# mainboard.net
KiCad netlist of a schematic drawn in EAGLE
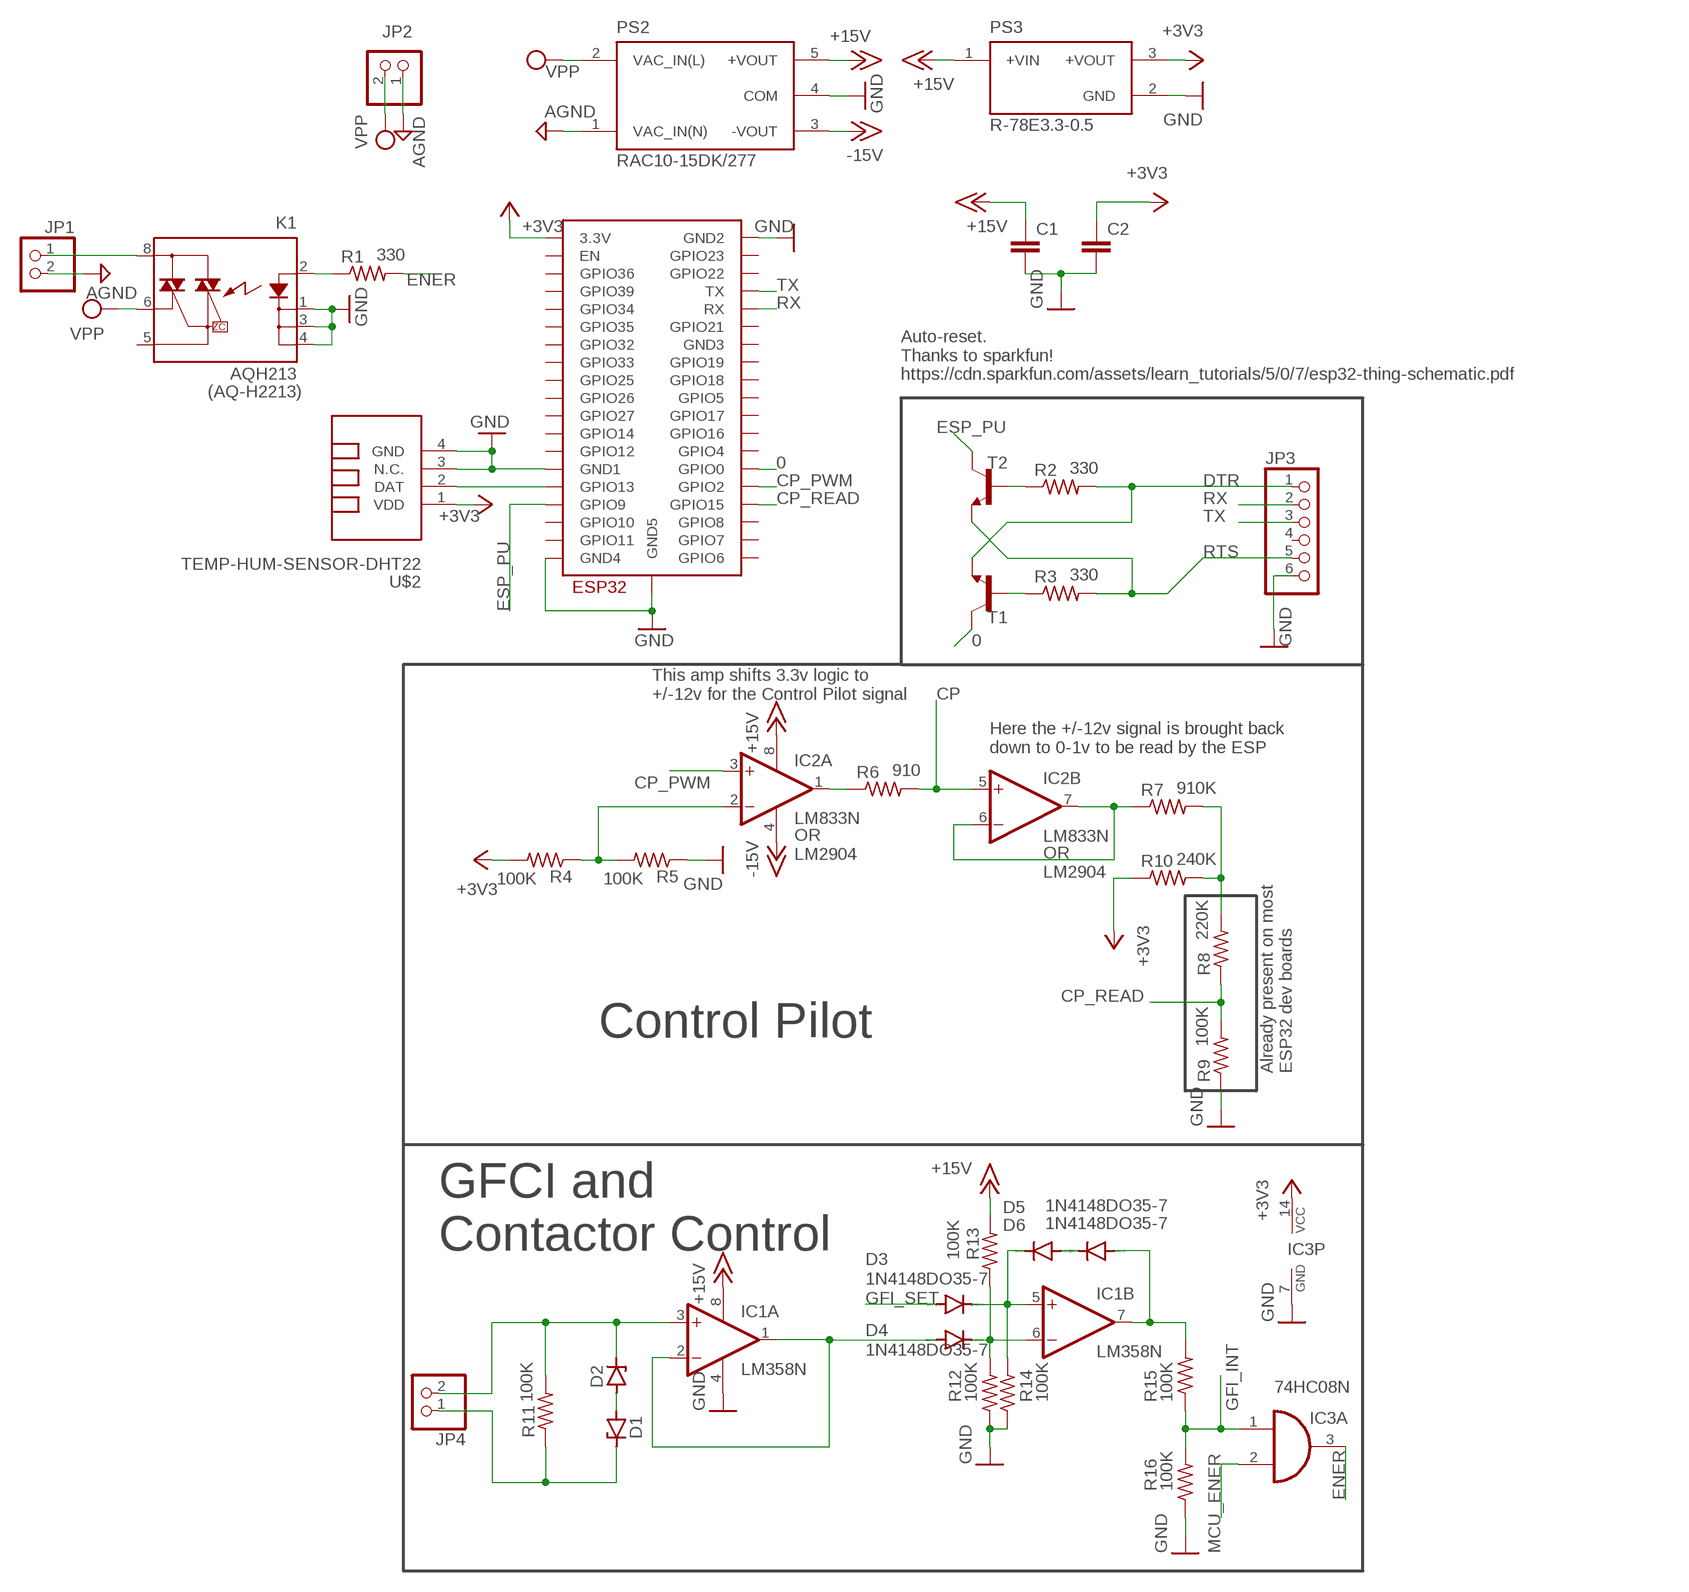
[diagram p0: schematic, sheet 1]

(export (version "E")
  (design (tool "Eeschema 10.0.6"))
  (components
    (comp (ref "C1")
      (value "C-EU025-025X050")
      (footprint "eagle-import:C025-025X050")
      (libsource (lib "eagle-import") (part "C-EU025-025X050"))
    )
    (comp (ref "C2")
      (value "C-EU025-025X050")
      (footprint "eagle-import:C025-025X050")
      (libsource (lib "eagle-import") (part "C-EU025-025X050"))
    )
    (comp (ref "D1")
      (value "ZENER-DIODEDO34-7")
      (footprint "eagle-import:DO34Z7")
      (libsource (lib "eagle-import") (part "ZENER-DIODEDO34-7"))
    )
    (comp (ref "D2")
      (value "ZENER-DIODEDO34-7")
      (footprint "eagle-import:DO34Z7")
      (libsource (lib "eagle-import") (part "ZENER-DIODEDO34-7"))
    )
    (comp (ref "D3")
      (value "1N4148DO35-7")
      (footprint "eagle-import:DO35-7")
      (libsource (lib "eagle-import") (part "1N4148DO35-7"))
    )
    (comp (ref "D4")
      (value "1N4148DO35-7")
      (footprint "eagle-import:DO35-7")
      (libsource (lib "eagle-import") (part "1N4148DO35-7"))
    )
    (comp (ref "D5")
      (value "1N4148DO35-7")
      (footprint "eagle-import:DO35-7")
      (libsource (lib "eagle-import") (part "1N4148DO35-7"))
    )
    (comp (ref "D6")
      (value "1N4148DO35-7")
      (footprint "eagle-import:DO35-7")
      (libsource (lib "eagle-import") (part "1N4148DO35-7"))
    )
    (comp (ref "IC1")
      (value "LM358N")
      (footprint "eagle-import:DIL08")
      (libsource (lib "eagle-import") (part "LM358N"))
    )
    (comp (ref "IC2")
      (value "LM833N")
      (footprint "eagle-import:DIL08")
      (libsource (lib "eagle-import") (part "LM833N"))
    )
    (comp (ref "IC3")
      (value "74HC08N")
      (footprint "eagle-import:DIL14")
      (libsource (lib "eagle-import") (part "7408NHC"))
    )
    (comp (ref "JP1")
      (value "PINHD-1X2")
      (footprint "eagle-import:1X02")
      (libsource (lib "eagle-import") (part "PINHD-1X2"))
    )
    (comp (ref "JP2")
      (value "PINHD-1X2")
      (footprint "eagle-import:1X02")
      (libsource (lib "eagle-import") (part "PINHD-1X2"))
    )
    (comp (ref "JP3")
      (value "PINHD-1X6")
      (footprint "eagle-import:1X06")
      (libsource (lib "eagle-import") (part "PINHD-1X6"))
    )
    (comp (ref "JP4")
      (value "PINHD-1X2")
      (footprint "eagle-import:1X02")
      (libsource (lib "eagle-import") (part "PINHD-1X2"))
    )
    (comp (ref "K1")
      (value "AQH213")
      (footprint "eagle-import:DIL07")
      (libsource (lib "eagle-import") (part "AQH213"))
    )
    (comp (ref "PS2")
      (value "RAC10-15DK/277")
      (footprint "eagle-import:CONV_RAC10-15DK_277")
      (fields (field (name "DIGI-KEY_PART_NUMBER") "945-3126-5-ND") (field (name "MF") "Recom Power"))
      (libsource (lib "eagle-import") (part "RAC10-15DK/277"))
    )
    (comp (ref "PS3")
      (value "R-78E3.3-0.5")
      (footprint "eagle-import:CONV_R-78E3.3-0.5")
      (fields (field (name "DIGI-KEY_PART_NUMBER") "945-1661-5-ND") (field (name "MF") "Recom Power"))
      (libsource (lib "eagle-import") (part "R-78E3.3-0.5"))
    )
    (comp (ref "R1")
      (value "330")
      (footprint "eagle-import:0204_7")
      (libsource (lib "eagle-import") (part "R-US_0204/7"))
    )
    (comp (ref "R2")
      (value "330")
      (footprint "eagle-import:0204_7")
      (libsource (lib "eagle-import") (part "R-US_0204/7"))
    )
    (comp (ref "R3")
      (value "330")
      (footprint "eagle-import:0204_7")
      (libsource (lib "eagle-import") (part "R-US_0204/7"))
    )
    (comp (ref "R4")
      (value "100K")
      (footprint "eagle-import:0204_7")
      (libsource (lib "eagle-import") (part "R-US_0204/7"))
    )
    (comp (ref "R5")
      (value "100K")
      (footprint "eagle-import:0204_7")
      (libsource (lib "eagle-import") (part "R-US_0204/7"))
    )
    (comp (ref "R6")
      (value "910")
      (footprint "eagle-import:0204_7")
      (libsource (lib "eagle-import") (part "R-US_0204/7"))
    )
    (comp (ref "R7")
      (value "910K")
      (footprint "eagle-import:0204_7")
      (libsource (lib "eagle-import") (part "R-US_0204/7"))
    )
    (comp (ref "R8")
      (value "220K")
      (footprint "eagle-import:0204_7")
      (libsource (lib "eagle-import") (part "R-US_0204/7"))
    )
    (comp (ref "R9")
      (value "100K")
      (footprint "eagle-import:0204_7")
      (libsource (lib "eagle-import") (part "R-US_0204/7"))
    )
    (comp (ref "R10")
      (value "240K")
      (footprint "eagle-import:0204_7")
      (libsource (lib "eagle-import") (part "R-US_0204/7"))
    )
    (comp (ref "R11")
      (value "100K")
      (footprint "eagle-import:0204_7")
      (libsource (lib "eagle-import") (part "R-US_0204/7"))
    )
    (comp (ref "R12")
      (value "100K")
      (footprint "eagle-import:0204_7")
      (libsource (lib "eagle-import") (part "R-US_0204/7"))
    )
    (comp (ref "R13")
      (value "100K")
      (footprint "eagle-import:0204_7")
      (libsource (lib "eagle-import") (part "R-US_0204/7"))
    )
    (comp (ref "R14")
      (value "100K")
      (footprint "eagle-import:0204_7")
      (libsource (lib "eagle-import") (part "R-US_0204/7"))
    )
    (comp (ref "R15")
      (value "100K")
      (footprint "eagle-import:0204_7")
      (libsource (lib "eagle-import") (part "R-US_0204/7"))
    )
    (comp (ref "R16")
      (value "100K")
      (footprint "eagle-import:0204_7")
      (libsource (lib "eagle-import") (part "R-US_0204/7"))
    )
    (comp (ref "T1")
      (value "MMBT3904LT1-NPN-SOT23-BEC")
      (footprint "eagle-import:SOT23-BEC")
      (libsource (lib "eagle-import") (part "-NPN-SOT23-BECMMBT3904LT1"))
    )
    (comp (ref "T2")
      (value "MMBT3904LT1-NPN-SOT23-BEC")
      (footprint "eagle-import:SOT23-BEC")
      (libsource (lib "eagle-import") (part "-NPN-SOT23-BECMMBT3904LT1"))
    )
    (comp (ref "U$1")
      (value "ESP32-WROOM")
      (footprint "eagle-import:ESP32-WROOM")
      (libsource (lib "eagle-import") (part "ESP32-WROOM"))
    )
    (comp (ref "U$2")
      (value "TEMP-HUM-SENSOR-DHT22")
      (footprint "eagle-import:TEMP-HUM-SENSOR-DHT22")
      (libsource (lib "eagle-import") (part "TEMP-HUM-SENSOR-DHT22"))
    )
  )
  (nets
    (net (code "1") (name "+3V3") (class "Default")
      (node (ref "C2") (pin "1") (pinfunction "1_1") (pintype "passive"))
      (node (ref "IC3") (pin "14") (pinfunction "VCC_14") (pintype "power_in"))
      (node (ref "PS3") (pin "3") (pinfunction "+VOUT_3") (pintype "output"))
      (node (ref "R10") (pin "1") (pinfunction "1_1") (pintype "passive"))
      (node (ref "R4") (pin "2") (pinfunction "2_2") (pintype "passive"))
      (node (ref "U$1") (pin "3V3") (pinfunction "3.3V_3V3") (pintype "bidirectional"))
      (node (ref "U$2") (pin "1") (pinfunction "VDD_1") (pintype "power_in"))
    )
    (net (code "2") (name "+15V") (class "Default")
      (node (ref "C1") (pin "1") (pinfunction "1_1") (pintype "passive"))
      (node (ref "IC1") (pin "8") (pinfunction "V+_8") (pintype "power_in"))
      (node (ref "IC2") (pin "8") (pinfunction "V+_8") (pintype "power_in"))
      (node (ref "PS2") (pin "5") (pinfunction "+VOUT_5") (pintype "output"))
      (node (ref "PS3") (pin "1") (pinfunction "+VIN_1") (pintype "input"))
      (node (ref "R13") (pin "2") (pinfunction "2_2") (pintype "passive"))
    )
    (net (code "3") (name "-15V") (class "Default")
      (node (ref "IC2") (pin "4") (pinfunction "V-_4") (pintype "power_in"))
      (node (ref "PS2") (pin "3") (pinfunction "-VOUT_3") (pintype "output"))
    )
    (net (code "4") (name "/0") (class "Default")
      (node (ref "T1") (pin "C") (pinfunction "C_C") (pintype "passive"))
      (node (ref "U$1") (pin "IO0") (pinfunction "GPIO0_IO0") (pintype "bidirectional"))
    )
    (net (code "5") (name "/CP") (class "Default")
      (node (ref "IC2") (pin "5") (pinfunction "+IN_5") (pintype "input"))
      (node (ref "R6") (pin "2") (pinfunction "2_2") (pintype "passive"))
    )
    (net (code "6") (name "/CP_PWM") (class "Default")
      (node (ref "IC2") (pin "3") (pinfunction "+IN_3") (pintype "input"))
      (node (ref "U$1") (pin "IO2") (pinfunction "GPIO2_IO2") (pintype "bidirectional"))
    )
    (net (code "7") (name "/CP_READ") (class "Default")
      (node (ref "R8") (pin "1") (pinfunction "1_1") (pintype "passive"))
      (node (ref "R9") (pin "2") (pinfunction "2_2") (pintype "passive"))
      (node (ref "U$1") (pin "IO15") (pinfunction "GPIO15_IO15") (pintype "bidirectional"))
    )
    (net (code "8") (name "/DTR") (class "Default")
      (node (ref "JP3") (pin "1") (pinfunction "1_1") (pintype "passive"))
      (node (ref "R2") (pin "2") (pinfunction "2_2") (pintype "passive"))
      (node (ref "T1") (pin "E") (pinfunction "E_E") (pintype "passive"))
    )
    (net (code "9") (name "/ENER") (class "Default")
      (node (ref "IC3") (pin "3") (pinfunction "O_3") (pintype "output"))
      (node (ref "R1") (pin "2") (pinfunction "2_2") (pintype "passive"))
    )
    (net (code "10") (name "/ESP_PU") (class "Default")
      (node (ref "T2") (pin "C") (pinfunction "C_C") (pintype "passive"))
      (node (ref "U$1") (pin "SD2") (pinfunction "GPIO9_SD2") (pintype "bidirectional"))
    )
    (net (code "11") (name "/GFI_INT") (class "Default")
      (node (ref "IC3") (pin "1") (pinfunction "I0_1") (pintype "input"))
      (node (ref "R15") (pin "1") (pinfunction "1_1") (pintype "passive"))
      (node (ref "R16") (pin "2") (pinfunction "2_2") (pintype "passive"))
    )
    (net (code "12") (name "/GFI_SET") (class "Default")
      (node (ref "D3") (pin "A") (pinfunction "A_A") (pintype "passive"))
    )
    (net (code "13") (name "/MCU_ENER") (class "Default")
      (node (ref "IC3") (pin "2") (pinfunction "I1_2") (pintype "input"))
    )
    (net (code "14") (name "/RTS") (class "Default")
      (node (ref "JP3") (pin "5") (pinfunction "5_5") (pintype "passive"))
      (node (ref "R3") (pin "2") (pinfunction "2_2") (pintype "passive"))
      (node (ref "T2") (pin "E") (pinfunction "E_E") (pintype "passive"))
    )
    (net (code "15") (name "/RX") (class "Default")
      (node (ref "JP3") (pin "2") (pinfunction "2_2") (pintype "passive"))
      (node (ref "U$1") (pin "RX") (pinfunction "RX_RX") (pintype "bidirectional"))
    )
    (net (code "16") (name "/TX") (class "Default")
      (node (ref "JP3") (pin "3") (pinfunction "3_3") (pintype "passive"))
      (node (ref "U$1") (pin "TX") (pinfunction "TX_TX") (pintype "bidirectional"))
    )
    (net (code "17") (name "AGND") (class "Default")
      (node (ref "JP1") (pin "2") (pinfunction "2_2") (pintype "passive"))
      (node (ref "JP2") (pin "1") (pinfunction "1_1") (pintype "passive"))
      (node (ref "PS2") (pin "1") (pinfunction "VAC_IN(N)_1") (pintype "input"))
    )
    (net (code "18") (name "GND") (class "Default")
      (node (ref "C1") (pin "2") (pinfunction "2_2") (pintype "passive"))
      (node (ref "C2") (pin "2") (pinfunction "2_2") (pintype "passive"))
      (node (ref "IC1") (pin "4") (pinfunction "V-_4") (pintype "power_in"))
      (node (ref "IC3") (pin "7") (pinfunction "GND_7") (pintype "power_in"))
      (node (ref "JP3") (pin "6") (pinfunction "6_6") (pintype "passive"))
      (node (ref "K1") (pin "1") (pinfunction "K_1") (pintype "passive"))
      (node (ref "K1") (pin "3") (pinfunction "K1_3") (pintype "passive"))
      (node (ref "K1") (pin "4") (pinfunction "K2_4") (pintype "passive"))
      (node (ref "PS2") (pin "4") (pinfunction "COM_4") (pintype "power_in"))
      (node (ref "PS3") (pin "2") (pinfunction "GND_2") (pintype "power_in"))
      (node (ref "R12") (pin "1") (pinfunction "1_1") (pintype "passive"))
      (node (ref "R14") (pin "1") (pinfunction "1_1") (pintype "passive"))
      (node (ref "R16") (pin "1") (pinfunction "1_1") (pintype "passive"))
      (node (ref "R5") (pin "1") (pinfunction "1_1") (pintype "passive"))
      (node (ref "R9") (pin "1") (pinfunction "1_1") (pintype "passive"))
      (node (ref "U$1") (pin "GND1") (pinfunction "GND1_GND1") (pintype "bidirectional"))
      (node (ref "U$1") (pin "GND2") (pinfunction "GND2_GND2") (pintype "bidirectional"))
      (node (ref "U$1") (pin "GND4") (pinfunction "GND4_GND4") (pintype "bidirectional"))
      (node (ref "U$1") (pin "GND5") (pinfunction "GND5_GND5") (pintype "bidirectional"))
      (node (ref "U$2") (pin "3") (pinfunction "N.C._3") (pintype "passive"))
      (node (ref "U$2") (pin "4") (pinfunction "GND_4") (pintype "power_in"))
    )
    (net (code "19") (name "Net-(D1-PadA)") (class "Default")
      (node (ref "D1") (pin "A") (pinfunction "A_A") (pintype "passive"))
      (node (ref "D2") (pin "A") (pinfunction "A_A") (pintype "passive"))
    )
    (net (code "20") (name "Net-(D1-PadC)") (class "Default")
      (node (ref "D1") (pin "C") (pinfunction "C_C") (pintype "passive"))
      (node (ref "JP4") (pin "1") (pinfunction "1_1") (pintype "passive"))
      (node (ref "R11") (pin "1") (pinfunction "1_1") (pintype "passive"))
    )
    (net (code "21") (name "Net-(D5-PadA)") (class "Default")
      (node (ref "D5") (pin "A") (pinfunction "A_A") (pintype "passive"))
      (node (ref "D6") (pin "C") (pinfunction "C_C") (pintype "passive"))
    )
    (net (code "22") (name "Net-(IC1A-+IN)") (class "Default")
      (node (ref "D2") (pin "C") (pinfunction "C_C") (pintype "passive"))
      (node (ref "IC1") (pin "3") (pinfunction "+IN_3") (pintype "input"))
      (node (ref "JP4") (pin "2") (pinfunction "2_2") (pintype "passive"))
      (node (ref "R11") (pin "2") (pinfunction "2_2") (pintype "passive"))
    )
    (net (code "23") (name "Net-(IC1A--IN)") (class "Default")
      (node (ref "D4") (pin "A") (pinfunction "A_A") (pintype "passive"))
      (node (ref "IC1") (pin "1") (pinfunction "OUT_1") (pintype "output"))
      (node (ref "IC1") (pin "2") (pinfunction "-IN_2") (pintype "input"))
    )
    (net (code "24") (name "Net-(IC1B-+IN)") (class "Default")
      (node (ref "D3") (pin "C") (pinfunction "C_C") (pintype "passive"))
      (node (ref "D5") (pin "C") (pinfunction "C_C") (pintype "passive"))
      (node (ref "IC1") (pin "5") (pinfunction "+IN_5") (pintype "input"))
      (node (ref "R14") (pin "2") (pinfunction "2_2") (pintype "passive"))
    )
    (net (code "25") (name "Net-(IC1B--IN)") (class "Default")
      (node (ref "D4") (pin "C") (pinfunction "C_C") (pintype "passive"))
      (node (ref "IC1") (pin "6") (pinfunction "-IN_6") (pintype "input"))
      (node (ref "R12") (pin "2") (pinfunction "2_2") (pintype "passive"))
      (node (ref "R13") (pin "1") (pinfunction "1_1") (pintype "passive"))
    )
    (net (code "26") (name "Net-(IC1B-OUT)") (class "Default")
      (node (ref "D6") (pin "A") (pinfunction "A_A") (pintype "passive"))
      (node (ref "IC1") (pin "7") (pinfunction "OUT_7") (pintype "output"))
      (node (ref "R15") (pin "2") (pinfunction "2_2") (pintype "passive"))
    )
    (net (code "27") (name "Net-(IC2A--IN)") (class "Default")
      (node (ref "IC2") (pin "2") (pinfunction "-IN_2") (pintype "input"))
      (node (ref "R4") (pin "1") (pinfunction "1_1") (pintype "passive"))
      (node (ref "R5") (pin "2") (pinfunction "2_2") (pintype "passive"))
    )
    (net (code "28") (name "Net-(IC2A-OUT)") (class "Default")
      (node (ref "IC2") (pin "1") (pinfunction "OUT_1") (pintype "output"))
      (node (ref "R6") (pin "1") (pinfunction "1_1") (pintype "passive"))
    )
    (net (code "29") (name "Net-(IC2B--IN)") (class "Default")
      (node (ref "IC2") (pin "6") (pinfunction "-IN_6") (pintype "input"))
      (node (ref "IC2") (pin "7") (pinfunction "OUT_7") (pintype "output"))
      (node (ref "R7") (pin "1") (pinfunction "1_1") (pintype "passive"))
    )
    (net (code "30") (name "Net-(K1-A)") (class "Default")
      (node (ref "K1") (pin "2") (pinfunction "A_2") (pintype "passive"))
      (node (ref "R1") (pin "1") (pinfunction "1_1") (pintype "passive"))
    )
    (net (code "31") (name "Net-(K1-DS1)") (class "Default")
      (node (ref "JP1") (pin "1") (pinfunction "1_1") (pintype "passive"))
      (node (ref "K1") (pin "8") (pinfunction "DS1_8") (pintype "passive"))
    )
    (net (code "32") (name "Net-(R2-Pad1)") (class "Default")
      (node (ref "R2") (pin "1") (pinfunction "1_1") (pintype "passive"))
      (node (ref "T2") (pin "B") (pinfunction "B_B") (pintype "passive"))
    )
    (net (code "33") (name "Net-(R3-Pad1)") (class "Default")
      (node (ref "R3") (pin "1") (pinfunction "1_1") (pintype "passive"))
      (node (ref "T1") (pin "B") (pinfunction "B_B") (pintype "passive"))
    )
    (net (code "34") (name "Net-(R10-Pad2)") (class "Default")
      (node (ref "R10") (pin "2") (pinfunction "2_2") (pintype "passive"))
      (node (ref "R7") (pin "2") (pinfunction "2_2") (pintype "passive"))
      (node (ref "R8") (pin "2") (pinfunction "2_2") (pintype "passive"))
    )
    (net (code "35") (name "Net-(U$1-GPIO13)") (class "Default")
      (node (ref "U$1") (pin "IO13") (pinfunction "GPIO13_IO13") (pintype "bidirectional"))
      (node (ref "U$2") (pin "2") (pinfunction "DAT_2") (pintype "bidirectional"))
    )
    (net (code "36") (name "VPP") (class "Default")
      (node (ref "JP2") (pin "2") (pinfunction "2_2") (pintype "passive"))
      (node (ref "K1") (pin "6") (pinfunction "DS3_6") (pintype "passive"))
      (node (ref "PS2") (pin "2") (pinfunction "VAC_IN(L)_2") (pintype "input"))
    )
    (net (code "37") (name "unconnected-(JP3-Pad4)") (class "Default")
      (node (ref "JP3") (pin "4") (pinfunction "4_4") (pintype "passive"))
    )
    (net (code "38") (name "unconnected-(K1-DS2-Pad5)") (class "Default")
      (node (ref "K1") (pin "5") (pinfunction "DS2_5") (pintype "passive"))
    )
    (net (code "39") (name "unconnected-(U$1-GPIO4-PadIO4)") (class "Default")
      (node (ref "U$1") (pin "IO4") (pinfunction "GPIO4_IO4") (pintype "bidirectional"))
    )
    (net (code "40") (name "unconnected-(U$1-GPIO5-PadIO5)") (class "Default")
      (node (ref "U$1") (pin "IO5") (pinfunction "GPIO5_IO5") (pintype "bidirectional"))
    )
    (net (code "41") (name "unconnected-(U$1-GPIO6-PadCLK)") (class "Default")
      (node (ref "U$1") (pin "CLK") (pinfunction "GPIO6_CLK") (pintype "bidirectional"))
    )
    (net (code "42") (name "unconnected-(U$1-GPIO7-PadSD0)") (class "Default")
      (node (ref "U$1") (pin "SD0") (pinfunction "GPIO7_SD0") (pintype "bidirectional"))
    )
    (net (code "43") (name "unconnected-(U$1-GPIO8-PadSD1)") (class "Default")
      (node (ref "U$1") (pin "SD1") (pinfunction "GPIO8_SD1") (pintype "bidirectional"))
    )
    (net (code "44") (name "unconnected-(U$1-GPIO10-PadSD3)") (class "Default")
      (node (ref "U$1") (pin "SD3") (pinfunction "GPIO10_SD3") (pintype "bidirectional"))
    )
    (net (code "45") (name "unconnected-(U$1-GPIO11-PadCMD)") (class "Default")
      (node (ref "U$1") (pin "CMD") (pinfunction "GPIO11_CMD") (pintype "bidirectional"))
    )
    (net (code "46") (name "unconnected-(U$1-GPIO12-PadIO12)") (class "Default")
      (node (ref "U$1") (pin "IO12") (pinfunction "GPIO12_IO12") (pintype "bidirectional"))
    )
    (net (code "47") (name "unconnected-(U$1-GPIO14-PadIO14)") (class "Default")
      (node (ref "U$1") (pin "IO14") (pinfunction "GPIO14_IO14") (pintype "bidirectional"))
    )
    (net (code "48") (name "unconnected-(U$1-GPIO16-PadIO16)") (class "Default")
      (node (ref "U$1") (pin "IO16") (pinfunction "GPIO16_IO16") (pintype "bidirectional"))
    )
    (net (code "49") (name "unconnected-(U$1-GPIO17-PadIO17)") (class "Default")
      (node (ref "U$1") (pin "IO17") (pinfunction "GPIO17_IO17") (pintype "bidirectional"))
    )
    (net (code "50") (name "unconnected-(U$1-GPIO18-PadIO18)") (class "Default")
      (node (ref "U$1") (pin "IO18") (pinfunction "GPIO18_IO18") (pintype "bidirectional"))
    )
    (net (code "51") (name "unconnected-(U$1-GPIO19-PadIO19)") (class "Default")
      (node (ref "U$1") (pin "IO19") (pinfunction "GPIO19_IO19") (pintype "bidirectional"))
    )
    (net (code "52") (name "unconnected-(U$1-GPIO21-PadIO21)") (class "Default")
      (node (ref "U$1") (pin "IO21") (pinfunction "GPIO21_IO21") (pintype "bidirectional"))
    )
    (net (code "53") (name "unconnected-(U$1-GPIO22-PadIO22)") (class "Default")
      (node (ref "U$1") (pin "IO22") (pinfunction "GPIO22_IO22") (pintype "bidirectional"))
    )
    (net (code "54") (name "unconnected-(U$1-GPIO23-PadIO23)") (class "Default")
      (node (ref "U$1") (pin "IO23") (pinfunction "GPIO23_IO23") (pintype "bidirectional"))
    )
    (net (code "55") (name "unconnected-(U$1-GPIO25-PadIO25)") (class "Default")
      (node (ref "U$1") (pin "IO25") (pinfunction "GPIO25_IO25") (pintype "bidirectional"))
    )
    (net (code "56") (name "unconnected-(U$1-GPIO26-PadIO26)") (class "Default")
      (node (ref "U$1") (pin "IO26") (pinfunction "GPIO26_IO26") (pintype "bidirectional"))
    )
    (net (code "57") (name "unconnected-(U$1-GPIO27-PadIO27)") (class "Default")
      (node (ref "U$1") (pin "IO27") (pinfunction "GPIO27_IO27") (pintype "bidirectional"))
    )
    (net (code "58") (name "unconnected-(U$1-GPIO32-PadIO32)") (class "Default")
      (node (ref "U$1") (pin "IO32") (pinfunction "GPIO32_IO32") (pintype "bidirectional"))
    )
    (net (code "59") (name "unconnected-(U$1-GPIO33-PadIO33)") (class "Default")
      (node (ref "U$1") (pin "IO33") (pinfunction "GPIO33_IO33") (pintype "bidirectional"))
    )
    (net (code "60") (name "unconnected-(U$1-GPIO34-PadIO34)") (class "Default")
      (node (ref "U$1") (pin "IO34") (pinfunction "GPIO34_IO34") (pintype "bidirectional"))
    )
    (net (code "61") (name "unconnected-(U$1-GPIO35-PadIO35)") (class "Default")
      (node (ref "U$1") (pin "IO35") (pinfunction "GPIO35_IO35") (pintype "bidirectional"))
    )
    (net (code "62") (name "unconnected-(U$1-GPIO36-PadSENSOR_VP)") (class "Default")
      (node (ref "U$1") (pin "SENSOR_VP") (pinfunction "GPIO36_SENSOR_VP") (pintype "bidirectional"))
    )
    (net (code "63") (name "unconnected-(U$1-GPIO39-PadSENSOR_VN)") (class "Default")
      (node (ref "U$1") (pin "SENSOR_VN") (pinfunction "GPIO39_SENSOR_VN") (pintype "bidirectional"))
    )
    (net (code "64") (name "unconnected-(U$1-PadEN)") (class "Default")
      (node (ref "U$1") (pin "EN") (pinfunction "EN_EN") (pintype "bidirectional"))
    )
    (net (code "65") (name "unconnected-(U$1-PadGND3)") (class "Default")
      (node (ref "U$1") (pin "GND3") (pinfunction "GND3_GND3") (pintype "bidirectional"))
    )
  )
)
